# isolation.net
KiCad netlist of a schematic drawn in Altium Designer
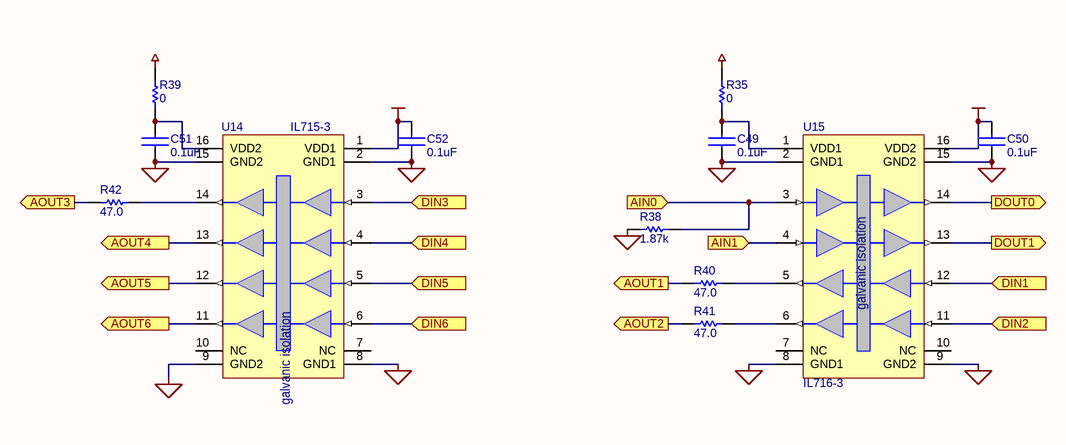
[diagram p0: isolation.SCHDOC]

(export (version "E")
  (design (tool "Eeschema 10.0.6"))
  (components
    (comp (ref "C49")
      (value "0.1uF")
      (footprint "0603")
      (description "Standard Capacitor")
      (fields (field (name "Comment") "CAPACITOR"))
      (libsource (lib "parts") (part "CAPACITOR"))
    )
    (comp (ref "C50")
      (value "0.1uF")
      (footprint "0603")
      (description "Standard Capacitor")
      (fields (field (name "Comment") "CAPACITOR"))
      (libsource (lib "parts") (part "CAPACITOR"))
    )
    (comp (ref "C51")
      (value "0.1uF")
      (footprint "0603")
      (description "Standard Capacitor")
      (fields (field (name "Comment") "CAPACITOR"))
      (libsource (lib "parts") (part "CAPACITOR"))
    )
    (comp (ref "C52")
      (value "0.1uF")
      (footprint "0603")
      (description "Standard Capacitor")
      (fields (field (name "Comment") "CAPACITOR"))
      (libsource (lib "parts") (part "CAPACITOR"))
    )
    (comp (ref "R35")
      (value "0")
      (footprint "0603")
      (description "Standard Passive Resistor")
      (fields (field (name "Comment") "RESISTOR"))
      (libsource (lib "parts") (part "RESISTOR"))
    )
    (comp (ref "R38")
      (value "1.87k")
      (footprint "0603")
      (description "Standard Passive Resistor")
      (fields (field (name "Comment") "RESISTOR"))
      (libsource (lib "parts") (part "RESISTOR"))
    )
    (comp (ref "R39")
      (value "0")
      (footprint "0603")
      (description "Standard Passive Resistor")
      (fields (field (name "Comment") "RESISTOR"))
      (libsource (lib "parts") (part "RESISTOR"))
    )
    (comp (ref "R40")
      (value "47.0")
      (footprint "0603")
      (description "Standard Passive Resistor")
      (fields (field (name "Comment") "RESISTOR"))
      (libsource (lib "parts") (part "RESISTOR"))
    )
    (comp (ref "R41")
      (value "47.0")
      (footprint "0603")
      (description "Standard Passive Resistor")
      (fields (field (name "Comment") "RESISTOR"))
      (libsource (lib "parts") (part "RESISTOR"))
    )
    (comp (ref "R42")
      (value "47.0")
      (footprint "0603")
      (description "Standard Passive Resistor")
      (fields (field (name "Comment") "RESISTOR"))
      (libsource (lib "parts") (part "RESISTOR"))
    )
    (comp (ref "U14")
      (value "IL715-3")
      (footprint "SO-G16/D10")
      (description "High speed digital coupler")
      (libsource (lib "parts") (part "IL715-3"))
    )
    (comp (ref "U15")
      (value "IL716-3")
      (footprint "SO-G16/D10")
      (description "High speed digital coupler")
      (libsource (lib "parts") (part "IL716-3"))
    )
  )
  (nets
    (net (code "1") (name "/AIN0") (class "Default")
      (node (ref "R38") (pin "2") (pintype "passive"))
      (node (ref "U15") (pin "3") (pinfunction "IN1_3") (pintype "input"))
    )
    (net (code "2") (name "/AIN1") (class "Default")
      (node (ref "U15") (pin "4") (pinfunction "IN2_4") (pintype "input"))
    )
    (net (code "3") (name "/AOUT1") (class "Default") (node (ref "R40") (pin "1") (pintype "passive")))
    (net (code "4") (name "/AOUT2") (class "Default") (node (ref "R41") (pin "1") (pintype "passive")))
    (net (code "5") (name "/AOUT3") (class "Default") (node (ref "R42") (pin "1") (pintype "passive")))
    (net (code "6") (name "/AOUT4") (class "Default")
      (node (ref "U14") (pin "13") (pinfunction "OUT2_13") (pintype "output"))
    )
    (net (code "7") (name "/AOUT5") (class "Default")
      (node (ref "U14") (pin "12") (pinfunction "OUT3_12") (pintype "output"))
    )
    (net (code "8") (name "/AOUT6") (class "Default")
      (node (ref "U14") (pin "11") (pinfunction "OUT4_11") (pintype "output"))
    )
    (net (code "9") (name "/DIN1") (class "Default")
      (node (ref "U15") (pin "12") (pinfunction "IN3_12") (pintype "input"))
    )
    (net (code "10") (name "/DIN2") (class "Default")
      (node (ref "U15") (pin "11") (pinfunction "IN4_11") (pintype "input"))
    )
    (net (code "11") (name "/DIN3") (class "Default")
      (node (ref "U14") (pin "3") (pinfunction "IN1_3") (pintype "input"))
    )
    (net (code "12") (name "/DIN4") (class "Default")
      (node (ref "U14") (pin "4") (pinfunction "IN2_4") (pintype "input"))
    )
    (net (code "13") (name "/DIN5") (class "Default")
      (node (ref "U14") (pin "5") (pinfunction "IN3_5") (pintype "input"))
    )
    (net (code "14") (name "/DIN6") (class "Default")
      (node (ref "U14") (pin "6") (pinfunction "IN4_6") (pintype "input"))
    )
    (net (code "15") (name "/DOUT0") (class "Default")
      (node (ref "U15") (pin "14") (pinfunction "OUT1_14") (pintype "output"))
    )
    (net (code "16") (name "/DOUT1") (class "Default")
      (node (ref "U15") (pin "13") (pinfunction "OUT2_13") (pintype "output"))
    )
    (net (code "17") (name "AGND") (class "Default")
      (node (ref "C49") (pin "1") (pintype "passive"))
      (node (ref "C51") (pin "1") (pintype "passive"))
      (node (ref "R38") (pin "1") (pintype "passive"))
      (node (ref "U14") (pin "15") (pinfunction "GND2_15") (pintype "power_in"))
      (node (ref "U14") (pin "9") (pinfunction "GND2_9") (pintype "power_in"))
      (node (ref "U15") (pin "2") (pinfunction "GND1_2") (pintype "power_in"))
      (node (ref "U15") (pin "8") (pinfunction "GND1_8") (pintype "power_in"))
    )
    (net (code "18") (name "AVDD") (class "Default")
      (node (ref "R35") (pin "2") (pintype "passive"))
      (node (ref "R39") (pin "2") (pintype "passive"))
    )
    (net (code "19") (name "GND") (class "Default")
      (node (ref "C50") (pin "1") (pintype "passive"))
      (node (ref "C52") (pin "1") (pintype "passive"))
      (node (ref "U14") (pin "2") (pinfunction "GND1_2") (pintype "power_in"))
      (node (ref "U14") (pin "8") (pinfunction "GND1_8") (pintype "power_in"))
      (node (ref "U15") (pin "15") (pinfunction "GND2_15") (pintype "power_in"))
      (node (ref "U15") (pin "9") (pinfunction "GND2_9") (pintype "power_in"))
    )
    (net (code "20") (name "Net-(U14-OUT1)") (class "Default")
      (node (ref "R42") (pin "2") (pintype "passive"))
      (node (ref "U14") (pin "14") (pinfunction "OUT1_14") (pintype "output"))
    )
    (net (code "21") (name "Net-(U14-VDD2)") (class "Default")
      (node (ref "C51") (pin "2") (pintype "passive"))
      (node (ref "R39") (pin "1") (pintype "passive"))
      (node (ref "U14") (pin "16") (pinfunction "VDD2_16") (pintype "power_in"))
    )
    (net (code "22") (name "Net-(U15-OUT3)") (class "Default")
      (node (ref "R40") (pin "2") (pintype "passive"))
      (node (ref "U15") (pin "5") (pinfunction "OUT3_5") (pintype "output"))
    )
    (net (code "23") (name "Net-(U15-OUT4)") (class "Default")
      (node (ref "R41") (pin "2") (pintype "passive"))
      (node (ref "U15") (pin "6") (pinfunction "OUT4_6") (pintype "output"))
    )
    (net (code "24") (name "Net-(U15-VDD1)") (class "Default")
      (node (ref "C49") (pin "2") (pintype "passive"))
      (node (ref "R35") (pin "1") (pintype "passive"))
      (node (ref "U15") (pin "1") (pinfunction "VDD1_1") (pintype "power_in"))
    )
    (net (code "25") (name "VCC") (class "Default")
      (node (ref "C50") (pin "2") (pintype "passive"))
      (node (ref "C52") (pin "2") (pintype "passive"))
      (node (ref "U14") (pin "1") (pinfunction "VDD1_1") (pintype "power_in"))
      (node (ref "U15") (pin "16") (pinfunction "VDD2_16") (pintype "power_in"))
    )
    (net (code "26") (name "unconnected-(U14-NC-Pad7)") (class "Default")
      (node (ref "U14") (pin "7") (pinfunction "NC_7") (pintype "passive"))
    )
    (net (code "27") (name "unconnected-(U14-NC-Pad10)") (class "Default")
      (node (ref "U14") (pin "10") (pinfunction "NC_10") (pintype "passive"))
    )
    (net (code "28") (name "unconnected-(U15-NC-Pad7)") (class "Default")
      (node (ref "U15") (pin "7") (pinfunction "NC_7") (pintype "passive"))
    )
    (net (code "29") (name "unconnected-(U15-NC-Pad10)") (class "Default")
      (node (ref "U15") (pin "10") (pinfunction "NC_10") (pintype "passive"))
    )
  )
)
